# AccessControl.net
KiCad netlist of a schematic drawn in EAGLE
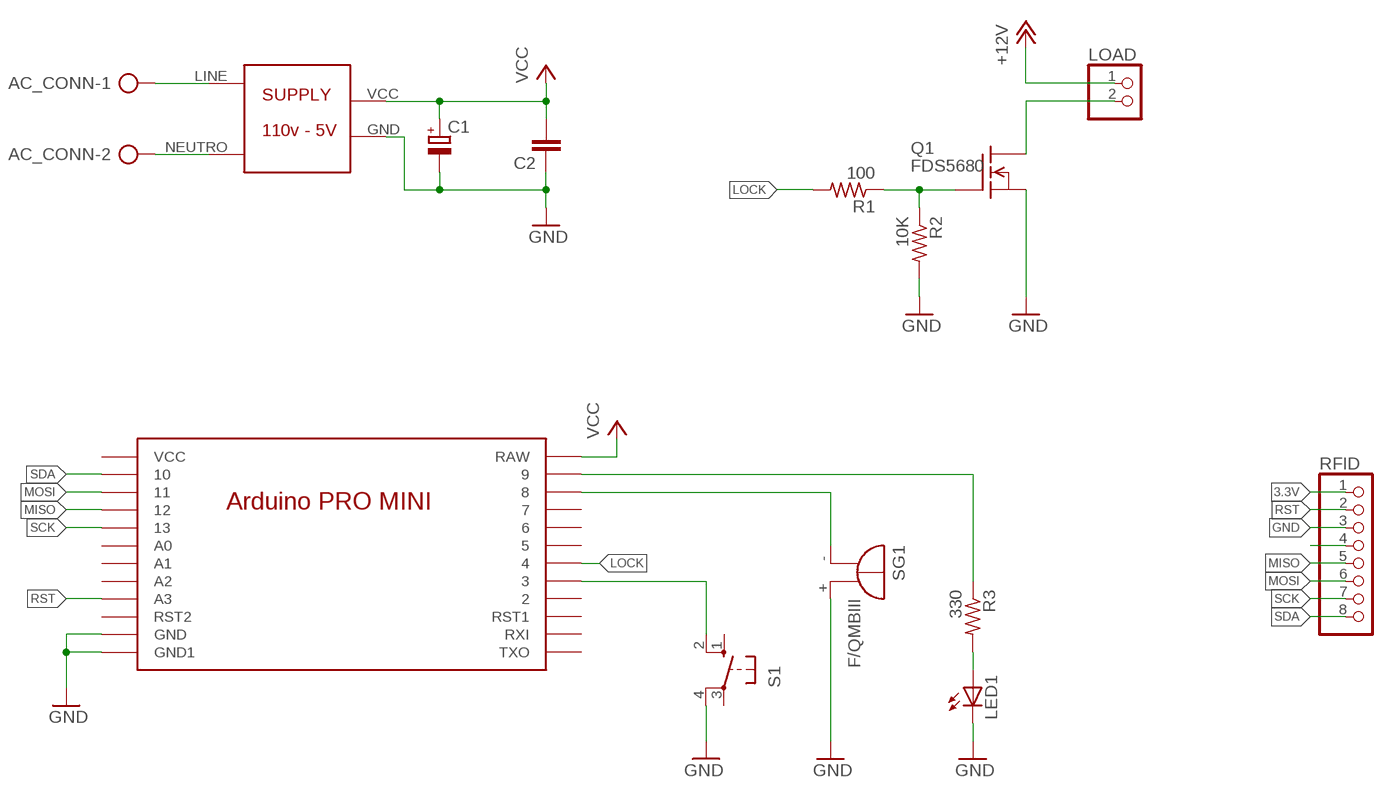
[diagram p0: schematic, sheet 1]

(export (version "E")
  (design (tool "Eeschema 10.0.6"))
  (components
    (comp (ref "AC_CONN")
      (value "AK300/2")
      (footprint "eagle-import:AK300_2")
      (libsource (lib "eagle-import") (part "AK300/2"))
    )
    (comp (ref "C1")
      (value "CPOL-EUE2.5-6")
      (footprint "eagle-import:E2,5-6")
      (libsource (lib "eagle-import") (part "CPOL-EUE2.5-6"))
    )
    (comp (ref "C2")
      (value "C2.5/2")
      (footprint "eagle-import:C2.5-2")
      (libsource (lib "eagle-import") (part "C2.5/2"))
    )
    (comp (ref "LED1")
      (value "LED3MM")
      (footprint "eagle-import:LED3MM")
      (libsource (lib "eagle-import") (part "LED3MM"))
    )
    (comp (ref "LOAD")
      (value "PINHD-1X2")
      (footprint "eagle-import:1X02")
      (libsource (lib "eagle-import") (part "PINHD-1X2"))
    )
    (comp (ref "Q1")
      (value "FDS5680")
      (footprint "eagle-import:SO-8")
      (libsource (lib "eagle-import") (part "FDS5680"))
    )
    (comp (ref "R1")
      (value "100")
      (footprint "eagle-import:0204_7")
      (libsource (lib "eagle-import") (part "R-US_0204/7"))
    )
    (comp (ref "R2")
      (value "10K")
      (footprint "eagle-import:0204_7")
      (libsource (lib "eagle-import") (part "R-US_0204/7"))
    )
    (comp (ref "R3")
      (value "330")
      (footprint "eagle-import:0204_7")
      (libsource (lib "eagle-import") (part "R-US_0204/7"))
    )
    (comp (ref "RFID")
      (value "PINHD-1X8")
      (footprint "eagle-import:1X08")
      (libsource (lib "eagle-import") (part "PINHD-1X8"))
    )
    (comp (ref "S1")
      (value "10-XX")
      (footprint "eagle-import:B3F-10XX")
      (fields (field (name "MPN") "B3F-1000"))
      (libsource (lib "eagle-import") (part "10-XX"))
    )
    (comp (ref "SG1")
      (value "F/QMBIII")
      (footprint "eagle-import:F_QMBIII")
      (libsource (lib "eagle-import") (part "F/QMBIII"))
    )
    (comp (ref "U$1")
      (value "NANO")
      (footprint "eagle-import:NANO")
      (libsource (lib "eagle-import") (part "NANO"))
    )
    (comp (ref "U$2")
      (value "SUPPLY5V")
      (footprint "eagle-import:SUPPLY5V")
      (libsource (lib "eagle-import") (part "SUPPLY5V"))
    )
  )
  (nets
    (net (code "1") (name "+12V") (class "Default")
      (node (ref "LOAD") (pin "1") (pinfunction "1_1") (pintype "passive"))
    )
    (net (code "2") (name "3.3V") (class "Default")
      (node (ref "RFID") (pin "1") (pinfunction "1_1") (pintype "passive"))
    )
    (net (code "3") (name "GND") (class "Default")
      (node (ref "C1") (pin "-") (pinfunction "-_-") (pintype "passive"))
      (node (ref "C2") (pin "1") (pinfunction "1_1") (pintype "passive"))
      (node (ref "LED1") (pin "K") (pinfunction "C_K") (pintype "passive"))
      (node (ref "Q1") (pin "1") (pinfunction "S_1") (pintype "passive"))
      (node (ref "Q1") (pin "2") (pinfunction "S_2") (pintype "passive"))
      (node (ref "Q1") (pin "3") (pinfunction "S_3") (pintype "passive"))
      (node (ref "R2") (pin "2") (pinfunction "2_2") (pintype "passive"))
      (node (ref "RFID") (pin "3") (pinfunction "3_3") (pintype "passive"))
      (node (ref "S1") (pin "4") (pinfunction "P1_4") (pintype "passive"))
      (node (ref "SG1") (pin "+") (pinfunction "-_+") (pintype "passive"))
      (node (ref "U$1") (pin "GND1") (pinfunction "GND_GND1") (pintype "bidirectional"))
      (node (ref "U$1") (pin "GND2") (pinfunction "GND1_GND2") (pintype "power_in"))
      (node (ref "U$2") (pin "GND") (pinfunction "GND_GND") (pintype "bidirectional"))
    )
    (net (code "4") (name "LOCK") (class "Default")
      (node (ref "R1") (pin "2") (pinfunction "2_2") (pintype "passive"))
      (node (ref "U$1") (pin "4") (pinfunction "4_4") (pintype "bidirectional"))
    )
    (net (code "5") (name "MISO") (class "Default")
      (node (ref "RFID") (pin "5") (pinfunction "5_5") (pintype "passive"))
      (node (ref "U$1") (pin "12") (pinfunction "12_12") (pintype "bidirectional"))
    )
    (net (code "6") (name "MOSI") (class "Default")
      (node (ref "RFID") (pin "6") (pinfunction "6_6") (pintype "passive"))
      (node (ref "U$1") (pin "11") (pinfunction "11_11") (pintype "bidirectional"))
    )
    (net (code "7") (name "Net-(AC_CONNA-KL)") (class "Default")
      (node (ref "AC_CONN") (pin "1") (pinfunction "KL_1") (pintype "passive"))
      (node (ref "U$2") (pin "LINE") (pinfunction "LINE_LINE") (pintype "bidirectional"))
    )
    (net (code "8") (name "Net-(AC_CONNB-KL)") (class "Default")
      (node (ref "AC_CONN") (pin "2") (pinfunction "KL_2") (pintype "passive"))
      (node (ref "U$2") (pin "NEUTRO") (pinfunction "NEUTRO_NEUTRO") (pintype "bidirectional"))
    )
    (net (code "9") (name "Net-(LED1-PadA)") (class "Default")
      (node (ref "LED1") (pin "A") (pinfunction "A_A") (pintype "passive"))
      (node (ref "R3") (pin "2") (pinfunction "2_2") (pintype "passive"))
    )
    (net (code "10") (name "Net-(LOAD-Pad2)") (class "Default")
      (node (ref "LOAD") (pin "2") (pinfunction "2_2") (pintype "passive"))
      (node (ref "Q1") (pin "5") (pinfunction "D_5") (pintype "passive"))
      (node (ref "Q1") (pin "6") (pinfunction "D_6") (pintype "passive"))
      (node (ref "Q1") (pin "7") (pinfunction "D_7") (pintype "passive"))
      (node (ref "Q1") (pin "8") (pinfunction "D_8") (pintype "passive"))
    )
    (net (code "11") (name "Net-(Q1-G)") (class "Default")
      (node (ref "Q1") (pin "4") (pinfunction "G_4") (pintype "passive"))
      (node (ref "R1") (pin "1") (pinfunction "1_1") (pintype "passive"))
      (node (ref "R2") (pin "1") (pinfunction "1_1") (pintype "passive"))
    )
    (net (code "12") (name "Net-(R3-Pad1)") (class "Default")
      (node (ref "R3") (pin "1") (pinfunction "1_1") (pintype "passive"))
      (node (ref "U$1") (pin "9") (pinfunction "9_9") (pintype "bidirectional"))
    )
    (net (code "13") (name "Net-(S1-S1)") (class "Default")
      (node (ref "S1") (pin "2") (pinfunction "S1_2") (pintype "passive"))
      (node (ref "U$1") (pin "3") (pinfunction "3_3") (pintype "bidirectional"))
    )
    (net (code "14") (name "Net-(SG1-+)") (class "Default")
      (node (ref "SG1") (pin "-") (pinfunction "+_-") (pintype "passive"))
      (node (ref "U$1") (pin "8") (pinfunction "8_8") (pintype "bidirectional"))
    )
    (net (code "15") (name "RST") (class "Default")
      (node (ref "RFID") (pin "2") (pinfunction "2_2") (pintype "passive"))
      (node (ref "U$1") (pin "A3") (pinfunction "A3_A3") (pintype "bidirectional"))
    )
    (net (code "16") (name "SCK") (class "Default")
      (node (ref "RFID") (pin "7") (pinfunction "7_7") (pintype "passive"))
      (node (ref "U$1") (pin "13") (pinfunction "13_13") (pintype "bidirectional"))
    )
    (net (code "17") (name "SDA") (class "Default")
      (node (ref "RFID") (pin "8") (pinfunction "8_8") (pintype "passive"))
      (node (ref "U$1") (pin "10") (pinfunction "10_10") (pintype "bidirectional"))
    )
    (net (code "18") (name "VCC") (class "Default")
      (node (ref "C1") (pin "+") (pinfunction "+_+") (pintype "passive"))
      (node (ref "C2") (pin "2") (pinfunction "2_2") (pintype "passive"))
      (node (ref "U$1") (pin "RAW") (pinfunction "RAW_RAW") (pintype "bidirectional"))
      (node (ref "U$2") (pin "VCC") (pinfunction "VCC_VCC") (pintype "bidirectional"))
    )
    (net (code "19") (name "unconnected-(RFID-Pad4)") (class "Default")
      (node (ref "RFID") (pin "4") (pinfunction "4_4") (pintype "passive"))
    )
    (net (code "20") (name "unconnected-(S1-P-Pad3)") (class "Default")
      (node (ref "S1") (pin "3") (pinfunction "P_3") (pintype "passive"))
    )
    (net (code "21") (name "unconnected-(S1-S-Pad1)") (class "Default")
      (node (ref "S1") (pin "1") (pinfunction "S_1") (pintype "passive"))
    )
    (net (code "22") (name "unconnected-(U$1-Pad2)") (class "Default")
      (node (ref "U$1") (pin "2") (pinfunction "2_2") (pintype "bidirectional"))
    )
    (net (code "23") (name "unconnected-(U$1-Pad5)") (class "Default")
      (node (ref "U$1") (pin "5") (pinfunction "5_5") (pintype "bidirectional"))
    )
    (net (code "24") (name "unconnected-(U$1-Pad6)") (class "Default")
      (node (ref "U$1") (pin "6") (pinfunction "6_6") (pintype "bidirectional"))
    )
    (net (code "25") (name "unconnected-(U$1-Pad7)") (class "Default")
      (node (ref "U$1") (pin "7") (pinfunction "7_7") (pintype "bidirectional"))
    )
    (net (code "26") (name "unconnected-(U$1-PadA0)") (class "Default")
      (node (ref "U$1") (pin "A0") (pinfunction "A0_A0") (pintype "bidirectional"))
    )
    (net (code "27") (name "unconnected-(U$1-PadA1)") (class "Default")
      (node (ref "U$1") (pin "A1") (pinfunction "A1_A1") (pintype "bidirectional"))
    )
    (net (code "28") (name "unconnected-(U$1-PadA2)") (class "Default")
      (node (ref "U$1") (pin "A2") (pinfunction "A2_A2") (pintype "bidirectional"))
    )
    (net (code "29") (name "unconnected-(U$1-PadRST1)") (class "Default")
      (node (ref "U$1") (pin "RST1") (pinfunction "RST1_RST1") (pintype "bidirectional"))
    )
    (net (code "30") (name "unconnected-(U$1-PadRST2)") (class "Default")
      (node (ref "U$1") (pin "RST2") (pinfunction "RST2_RST2") (pintype "bidirectional"))
    )
    (net (code "31") (name "unconnected-(U$1-PadRXI)") (class "Default")
      (node (ref "U$1") (pin "RXI") (pinfunction "RXI_RXI") (pintype "bidirectional"))
    )
    (net (code "32") (name "unconnected-(U$1-PadTXO)") (class "Default")
      (node (ref "U$1") (pin "TXO") (pinfunction "TXO_TXO") (pintype "bidirectional"))
    )
    (net (code "33") (name "unconnected-(U$1-PadVCC)") (class "Default")
      (node (ref "U$1") (pin "VCC") (pinfunction "VCC_VCC") (pintype "bidirectional"))
    )
  )
)
